# design.net
KiCad netlist of a schematic drawn in EasyEDA
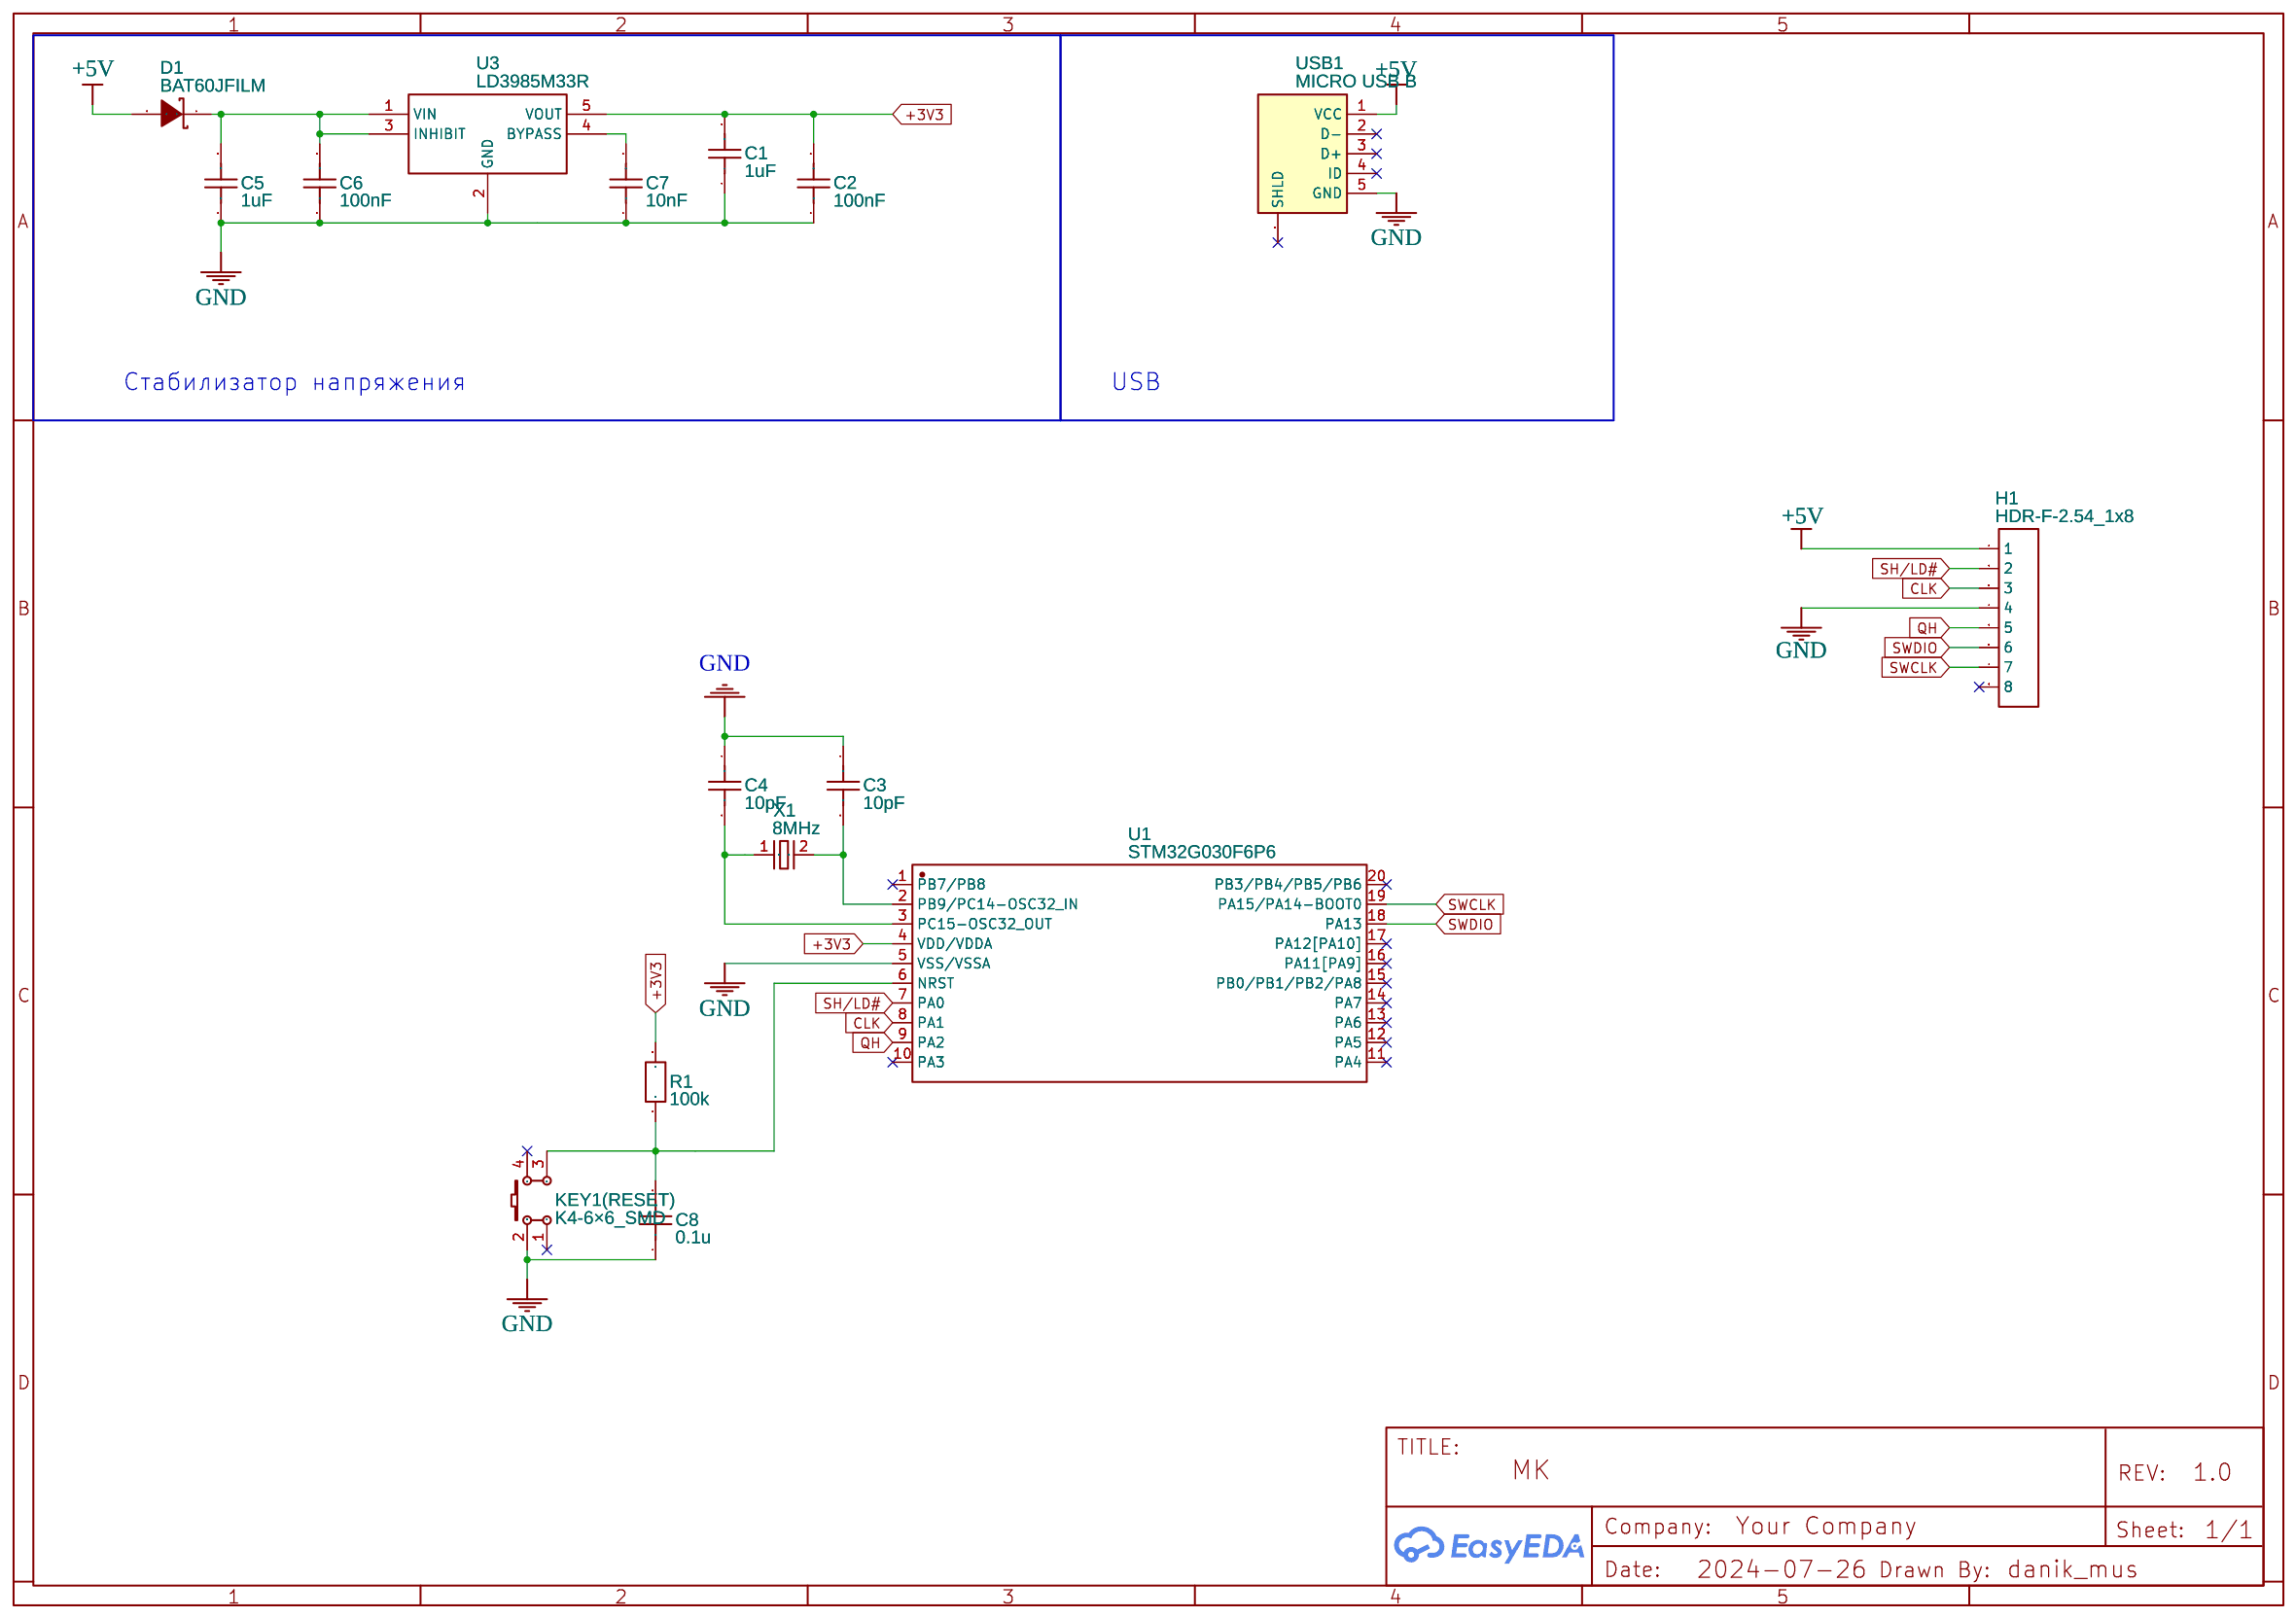
[diagram p0: schematic sheet]

(export (version "E")
  (design (tool "Eeschema 10.0.6"))
  (components
    (comp (ref "C1") (value "1uF") (libsource (lib "") (part "C_0603_US")))
    (comp (ref "C2") (value "100nF") (libsource (lib "") (part "C_0603_US")))
    (comp (ref "C3") (value "10pF") (libsource (lib "") (part "C_0603_US_1")))
    (comp (ref "C4") (value "10pF") (libsource (lib "") (part "C_0603_US_1")))
    (comp (ref "C5") (value "1uF") (libsource (lib "") (part "C_0603_US")))
    (comp (ref "C6") (value "100nF") (libsource (lib "") (part "C_0603_US")))
    (comp (ref "C7") (value "10nF") (libsource (lib "") (part "C_0603_US")))
    (comp (ref "C8") (value "0.1u") (libsource (lib "") (part "C_0603_US")))
    (comp (ref "D1")
      (value "BAT60JFILM")
      (fields (field (name "Manufacturer") "ST(意法半导体)"))
      (libsource (lib "") (part "BAT60JFILM"))
    )
    (comp (ref "H1") (value "HDR-F-2.54_1x8") (libsource (lib "") (part "HDR-F-2.54_1x8")))
    (comp (ref "KEY1(RESET)")
      (value "K4-6×6_SMD")
      (fields (field (name "Manufacturer Part") "K2-6639SP-D4SC-04") (field (name "Manufacturer") "韩国韩荣"))
      (libsource (lib "") (part "K4-6×6_SMD"))
    )
    (comp (ref "R1") (value "100k") (libsource (lib "") (part "R_0603_EU")))
    (comp (ref "U1")
      (value "STM32G030F6P6")
      (fields (field (name "Manufacturer") "ST(意法半导体)"))
      (libsource (lib "") (part "STM32G030F6P6"))
    )
    (comp (ref "U3")
      (value "LD3985M33R")
      (fields (field (name "Manufacturer") "ST(意法半导体)"))
      (libsource (lib "") (part "LD3985M33R"))
    )
    (comp (ref "USB1")
      (value "MICRO USB B")
      (fields (field (name "Manufacturer Part") "U-F-M5SW-Y-3") (field (name "Manufacturer") "HRO"))
      (libsource (lib "") (part "MICRO USB B"))
    )
    (comp (ref "X1")
      (value "8MHz")
      (fields
        (field (name "Manufacturer Part") "NX3225GD-8MHZ-STD-CRA-3")
        (field (name "Manufacturer") "NDK")
      )
      (libsource (lib "") (part "NX3225GD-8MHZ-STD-CRA-3"))
    )
  )
  (nets
    (net (code "1") (name "+3V3") (class "Default")
      (node (ref "C1") (pin "2") (pinfunction "2_2") (pintype "unspecified"))
      (node (ref "C2") (pin "2") (pinfunction "2_2") (pintype "unspecified"))
      (node (ref "R1") (pin "2") (pinfunction "2_2") (pintype "unspecified"))
      (node (ref "U1") (pin "4") (pinfunction "VDD/VDDA_4") (pintype "unspecified"))
      (node (ref "U3") (pin "5") (pinfunction "VOUT_5") (pintype "passive"))
    )
    (net (code "2") (name "+5V") (class "Default")
      (node (ref "D1") (pin "2") (pinfunction "A_2") (pintype "unspecified"))
      (node (ref "H1") (pin "1") (pinfunction "1_1") (pintype "unspecified"))
      (node (ref "USB1") (pin "1") (pinfunction "VCC_1") (pintype "input"))
    )
    (net (code "3") (name "CLK") (class "Default")
      (node (ref "H1") (pin "3") (pinfunction "3_3") (pintype "unspecified"))
      (node (ref "U1") (pin "8") (pinfunction "PA1_8") (pintype "unspecified"))
    )
    (net (code "4") (name "GND") (class "Default")
      (node (ref "C1") (pin "1") (pinfunction "1_1") (pintype "unspecified"))
      (node (ref "C2") (pin "1") (pinfunction "1_1") (pintype "unspecified"))
      (node (ref "C3") (pin "1") (pinfunction "1_1") (pintype "unspecified"))
      (node (ref "C4") (pin "1") (pinfunction "1_1") (pintype "unspecified"))
      (node (ref "C5") (pin "1") (pinfunction "1_1") (pintype "unspecified"))
      (node (ref "C6") (pin "1") (pinfunction "1_1") (pintype "unspecified"))
      (node (ref "C7") (pin "1") (pinfunction "1_1") (pintype "unspecified"))
      (node (ref "C8") (pin "1") (pinfunction "1_1") (pintype "unspecified"))
      (node (ref "H1") (pin "4") (pinfunction "4_4") (pintype "unspecified"))
      (node (ref "KEY1(RESET)") (pin "2") (pinfunction "2_2") (pintype "unspecified"))
      (node (ref "U1") (pin "5") (pinfunction "VSS/VSSA_5") (pintype "unspecified"))
      (node (ref "U3") (pin "2") (pinfunction "GND_2") (pintype "passive"))
      (node (ref "USB1") (pin "5") (pinfunction "GND_5") (pintype "input"))
    )
    (net (code "5") (name "Net-(D1-K)") (class "Default")
      (node (ref "C5") (pin "2") (pinfunction "2_2") (pintype "unspecified"))
      (node (ref "C6") (pin "2") (pinfunction "2_2") (pintype "unspecified"))
      (node (ref "D1") (pin "1") (pinfunction "K_1") (pintype "unspecified"))
      (node (ref "U3") (pin "1") (pinfunction "VIN_1") (pintype "passive"))
      (node (ref "U3") (pin "3") (pinfunction "INHIBIT_3") (pintype "unspecified"))
    )
    (net (code "6") (name "Net-(U1-NRST)") (class "Default")
      (node (ref "C8") (pin "2") (pinfunction "2_2") (pintype "unspecified"))
      (node (ref "KEY1(RESET)") (pin "3") (pinfunction "3_3") (pintype "unspecified"))
      (node (ref "R1") (pin "1") (pinfunction "1_1") (pintype "unspecified"))
      (node (ref "U1") (pin "6") (pinfunction "NRST_6") (pintype "unspecified"))
    )
    (net (code "7") (name "Net-(U1-PB9{slash}PC14-OSC32_IN)") (class "Default")
      (node (ref "C3") (pin "2") (pinfunction "2_2") (pintype "unspecified"))
      (node (ref "U1") (pin "2") (pinfunction "PB9/PC14-OSC32_IN_2") (pintype "unspecified"))
      (node (ref "X1") (pin "2") (pinfunction "GND_2") (pintype "input"))
    )
    (net (code "8") (name "Net-(U1-PC15-OSC32_OUT)") (class "Default")
      (node (ref "C4") (pin "2") (pinfunction "2_2") (pintype "unspecified"))
      (node (ref "U1") (pin "3") (pinfunction "PC15-OSC32_OUT_3") (pintype "unspecified"))
      (node (ref "X1") (pin "1") (pinfunction "1_1") (pintype "input"))
    )
    (net (code "9") (name "Net-(U3-BYPASS)") (class "Default")
      (node (ref "C7") (pin "2") (pinfunction "2_2") (pintype "unspecified"))
      (node (ref "U3") (pin "4") (pinfunction "BYPASS_4") (pintype "unspecified"))
    )
    (net (code "10") (name "QH") (class "Default")
      (node (ref "H1") (pin "5") (pinfunction "5_5") (pintype "unspecified"))
      (node (ref "U1") (pin "9") (pinfunction "PA2_9") (pintype "unspecified"))
    )
    (net (code "11") (name "SH{slash}LD#") (class "Default")
      (node (ref "H1") (pin "2") (pinfunction "2_2") (pintype "unspecified"))
      (node (ref "U1") (pin "7") (pinfunction "PA0_7") (pintype "unspecified"))
    )
    (net (code "12") (name "SWCLK") (class "Default")
      (node (ref "H1") (pin "7") (pinfunction "7_7") (pintype "unspecified"))
      (node (ref "U1") (pin "19") (pinfunction "PA15/PA14-BOOT0_19") (pintype "unspecified"))
    )
    (net (code "13") (name "SWDIO") (class "Default")
      (node (ref "H1") (pin "6") (pinfunction "6_6") (pintype "unspecified"))
      (node (ref "U1") (pin "18") (pinfunction "PA13_18") (pintype "unspecified"))
    )
    (net (code "14") (name "unconnected-(H1-Pad8)") (class "Default")
      (node (ref "H1") (pin "8") (pinfunction "8_8") (pintype "unspecified+no_connect"))
    )
    (net (code "15") (name "unconnected-(KEY1(RESET)-Pad1)") (class "Default")
      (node (ref "KEY1(RESET)") (pin "1") (pinfunction "1_1") (pintype "unspecified+no_connect"))
    )
    (net (code "16") (name "unconnected-(KEY1(RESET)-Pad4)") (class "Default")
      (node (ref "KEY1(RESET)") (pin "4") (pinfunction "4_4") (pintype "unspecified+no_connect"))
    )
    (net (code "17") (name "unconnected-(U1-PA3-Pad10)") (class "Default")
      (node (ref "U1") (pin "10") (pinfunction "PA3_10") (pintype "unspecified+no_connect"))
    )
    (net (code "18") (name "unconnected-(U1-PA4-Pad11)") (class "Default")
      (node (ref "U1") (pin "11") (pinfunction "PA4_11") (pintype "unspecified+no_connect"))
    )
    (net (code "19") (name "unconnected-(U1-PA5-Pad12)") (class "Default")
      (node (ref "U1") (pin "12") (pinfunction "PA5_12") (pintype "unspecified+no_connect"))
    )
    (net (code "20") (name "unconnected-(U1-PA6-Pad13)") (class "Default")
      (node (ref "U1") (pin "13") (pinfunction "PA6_13") (pintype "unspecified+no_connect"))
    )
    (net (code "21") (name "unconnected-(U1-PA7-Pad14)") (class "Default")
      (node (ref "U1") (pin "14") (pinfunction "PA7_14") (pintype "unspecified+no_connect"))
    )
    (net (code "22") (name "unconnected-(U1-PA11[PA9]-Pad16)") (class "Default")
      (node (ref "U1") (pin "16") (pinfunction "PA11[PA9]_16") (pintype "unspecified+no_connect"))
    )
    (net (code "23") (name "unconnected-(U1-PA12[PA10]-Pad17)") (class "Default")
      (node (ref "U1") (pin "17") (pinfunction "PA12[PA10]_17") (pintype "unspecified+no_connect"))
    )
    (net (code "24") (name "unconnected-(U1-PB0{slash}PB1{slash}PB2{slash}PA8-Pad15)") (class "Default")
      (node (ref "U1") (pin "15") (pinfunction "PB0/PB1/PB2/PA8_15") (pintype "unspecified+no_connect"))
    )
    (net (code "25") (name "unconnected-(U1-PB3{slash}PB4{slash}PB5{slash}PB6-Pad20)") (class "Default")
      (node (ref "U1") (pin "20") (pinfunction "PB3/PB4/PB5/PB6_20") (pintype "unspecified+no_connect"))
    )
    (net (code "26") (name "unconnected-(U1-PB7{slash}PB8-Pad1)") (class "Default")
      (node (ref "U1") (pin "1") (pinfunction "PB7/PB8_1") (pintype "unspecified+no_connect"))
    )
    (net (code "27") (name "unconnected-(USB1-D+-Pad3)") (class "Default")
      (node (ref "USB1") (pin "3") (pinfunction "D+_3") (pintype "input+no_connect"))
    )
    (net (code "28") (name "unconnected-(USB1-D--Pad2)") (class "Default")
      (node (ref "USB1") (pin "2") (pinfunction "D-_2") (pintype "input+no_connect"))
    )
    (net (code "29") (name "unconnected-(USB1-ID-Pad4)") (class "Default")
      (node (ref "USB1") (pin "4") (pinfunction "ID_4") (pintype "input+no_connect"))
    )
    (net (code "30") (name "unconnected-(USB1-SHLD-Pad6)") (class "Default")
      (node (ref "USB1") (pin "6") (pinfunction "SHLD_6") (pintype "input+no_connect"))
    )
  )
)
